# breakout.net
KiCad netlist of a schematic drawn in EAGLE
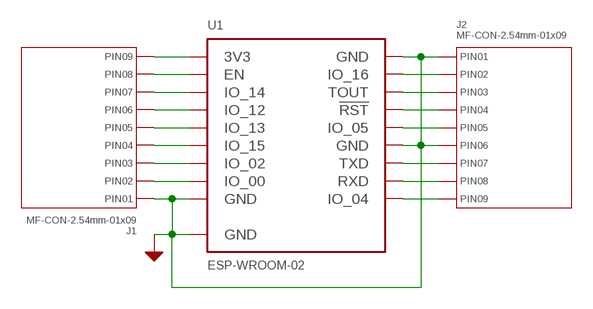
[diagram p0: schematic, sheet 1]

(export (version "E")
  (design (tool "Eeschema 10.0.6"))
  (components
    (comp (ref "J1")
      (value "MF-CON-2.54mm-01x09")
      (footprint "eagle-import:PTH_2.54MM_01X09")
      (fields (field (name "HOUSEPART") "YES"))
      (libsource (lib "eagle-import") (part "CON_01X09_PTH_2.54MM"))
    )
    (comp (ref "J2")
      (value "MF-CON-2.54mm-01x09")
      (footprint "eagle-import:PTH_2.54MM_01X09")
      (fields (field (name "HOUSEPART") "YES"))
      (libsource (lib "eagle-import") (part "CON_01X09_PTH_2.54MM"))
    )
    (comp (ref "U1")
      (value "ESP-WROOM-02")
      (footprint "eagle-import:ESP-WROOM-02")
      (libsource (lib "eagle-import") (part "ESP-WROOM-02"))
    )
  )
  (nets
    (net (code "1") (name "GND_RAIL") (class "Default")
      (node (ref "J1") (pin "P$1") (pinfunction "PIN1_P$1") (pintype "bidirectional"))
      (node (ref "J2") (pin "P$1") (pinfunction "PIN1_P$1") (pintype "bidirectional"))
      (node (ref "J2") (pin "P$6") (pinfunction "PIN6_P$6") (pintype "bidirectional"))
      (node (ref "U1") (pin "GND") (pinfunction "GND_GND") (pintype "power_in"))
      (node (ref "U1") (pin "GND@13") (pinfunction "GND_GND@13") (pintype "power_in"))
      (node (ref "U1") (pin "GND@18") (pinfunction "GND_GND@18") (pintype "power_in"))
      (node (ref "U1") (pin "GND@9") (pinfunction "GND_GND@9") (pintype "power_in"))
    )
    (net (code "2") (name "Net-(J1-PIN2)") (class "Default")
      (node (ref "J1") (pin "P$2") (pinfunction "PIN2_P$2") (pintype "bidirectional"))
      (node (ref "U1") (pin "IO_00") (pinfunction "IO_00_IO_00") (pintype "bidirectional"))
    )
    (net (code "3") (name "Net-(J1-PIN3)") (class "Default")
      (node (ref "J1") (pin "P$3") (pinfunction "PIN3_P$3") (pintype "bidirectional"))
      (node (ref "U1") (pin "IO_02") (pinfunction "IO_02_IO_02") (pintype "bidirectional"))
    )
    (net (code "4") (name "Net-(J1-PIN4)") (class "Default")
      (node (ref "J1") (pin "P$4") (pinfunction "PIN4_P$4") (pintype "bidirectional"))
      (node (ref "U1") (pin "IO_15") (pinfunction "IO_15_IO_15") (pintype "bidirectional"))
    )
    (net (code "5") (name "Net-(J1-PIN5)") (class "Default")
      (node (ref "J1") (pin "P$5") (pinfunction "PIN5_P$5") (pintype "bidirectional"))
      (node (ref "U1") (pin "IO_13") (pinfunction "IO_13_IO_13") (pintype "bidirectional"))
    )
    (net (code "6") (name "Net-(J1-PIN6)") (class "Default")
      (node (ref "J1") (pin "P$6") (pinfunction "PIN6_P$6") (pintype "bidirectional"))
      (node (ref "U1") (pin "IO_12") (pinfunction "IO_12_IO_12") (pintype "bidirectional"))
    )
    (net (code "7") (name "Net-(J1-PIN7)") (class "Default")
      (node (ref "J1") (pin "P$7") (pinfunction "PIN7_P$7") (pintype "bidirectional"))
      (node (ref "U1") (pin "IO_14") (pinfunction "IO_14_IO_14") (pintype "bidirectional"))
    )
    (net (code "8") (name "Net-(J1-PIN8)") (class "Default")
      (node (ref "J1") (pin "P$8") (pinfunction "PIN8_P$8") (pintype "bidirectional"))
      (node (ref "U1") (pin "EN") (pinfunction "EN_EN") (pintype "input"))
    )
    (net (code "9") (name "Net-(J1-PIN9)") (class "Default")
      (node (ref "J1") (pin "P$9") (pinfunction "PIN9_P$9") (pintype "bidirectional"))
      (node (ref "U1") (pin "3V3") (pinfunction "3V3_3V3") (pintype "power_in"))
    )
    (net (code "10") (name "Net-(J2-PIN2)") (class "Default")
      (node (ref "J2") (pin "P$2") (pinfunction "PIN2_P$2") (pintype "bidirectional"))
      (node (ref "U1") (pin "IO_16") (pinfunction "IO_16_IO_16") (pintype "bidirectional"))
    )
    (net (code "11") (name "Net-(J2-PIN3)") (class "Default")
      (node (ref "J2") (pin "P$3") (pinfunction "PIN3_P$3") (pintype "bidirectional"))
      (node (ref "U1") (pin "TOUT") (pinfunction "TOUT_TOUT") (pintype "output"))
    )
    (net (code "12") (name "Net-(J2-PIN4)") (class "Default")
      (node (ref "J2") (pin "P$4") (pinfunction "PIN4_P$4") (pintype "bidirectional"))
      (node (ref "U1") (pin "RST") (pinfunction "~{RST}_RST") (pintype "input"))
    )
    (net (code "13") (name "Net-(J2-PIN5)") (class "Default")
      (node (ref "J2") (pin "P$5") (pinfunction "PIN5_P$5") (pintype "bidirectional"))
      (node (ref "U1") (pin "IO_05") (pinfunction "IO_05_IO_05") (pintype "bidirectional"))
    )
    (net (code "14") (name "Net-(J2-PIN7)") (class "Default")
      (node (ref "J2") (pin "P$7") (pinfunction "PIN7_P$7") (pintype "bidirectional"))
      (node (ref "U1") (pin "TXD") (pinfunction "TXD_TXD") (pintype "bidirectional"))
    )
    (net (code "15") (name "Net-(J2-PIN8)") (class "Default")
      (node (ref "J2") (pin "P$8") (pinfunction "PIN8_P$8") (pintype "bidirectional"))
      (node (ref "U1") (pin "RXD") (pinfunction "RXD_RXD") (pintype "bidirectional"))
    )
    (net (code "16") (name "Net-(J2-PIN9)") (class "Default")
      (node (ref "J2") (pin "P$9") (pinfunction "PIN9_P$9") (pintype "bidirectional"))
      (node (ref "U1") (pin "IO_04") (pinfunction "IO_04_IO_04") (pintype "bidirectional"))
    )
  )
)
